# GAT8_PCB.net
KiCad netlist of a schematic drawn in EAGLE
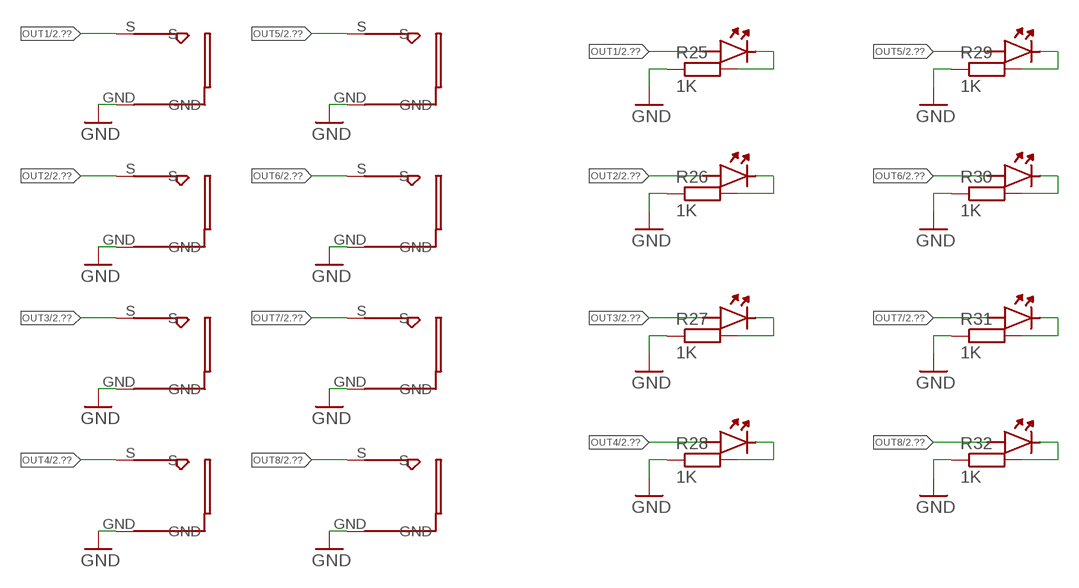
[diagram p0: schematic, sheet 1]
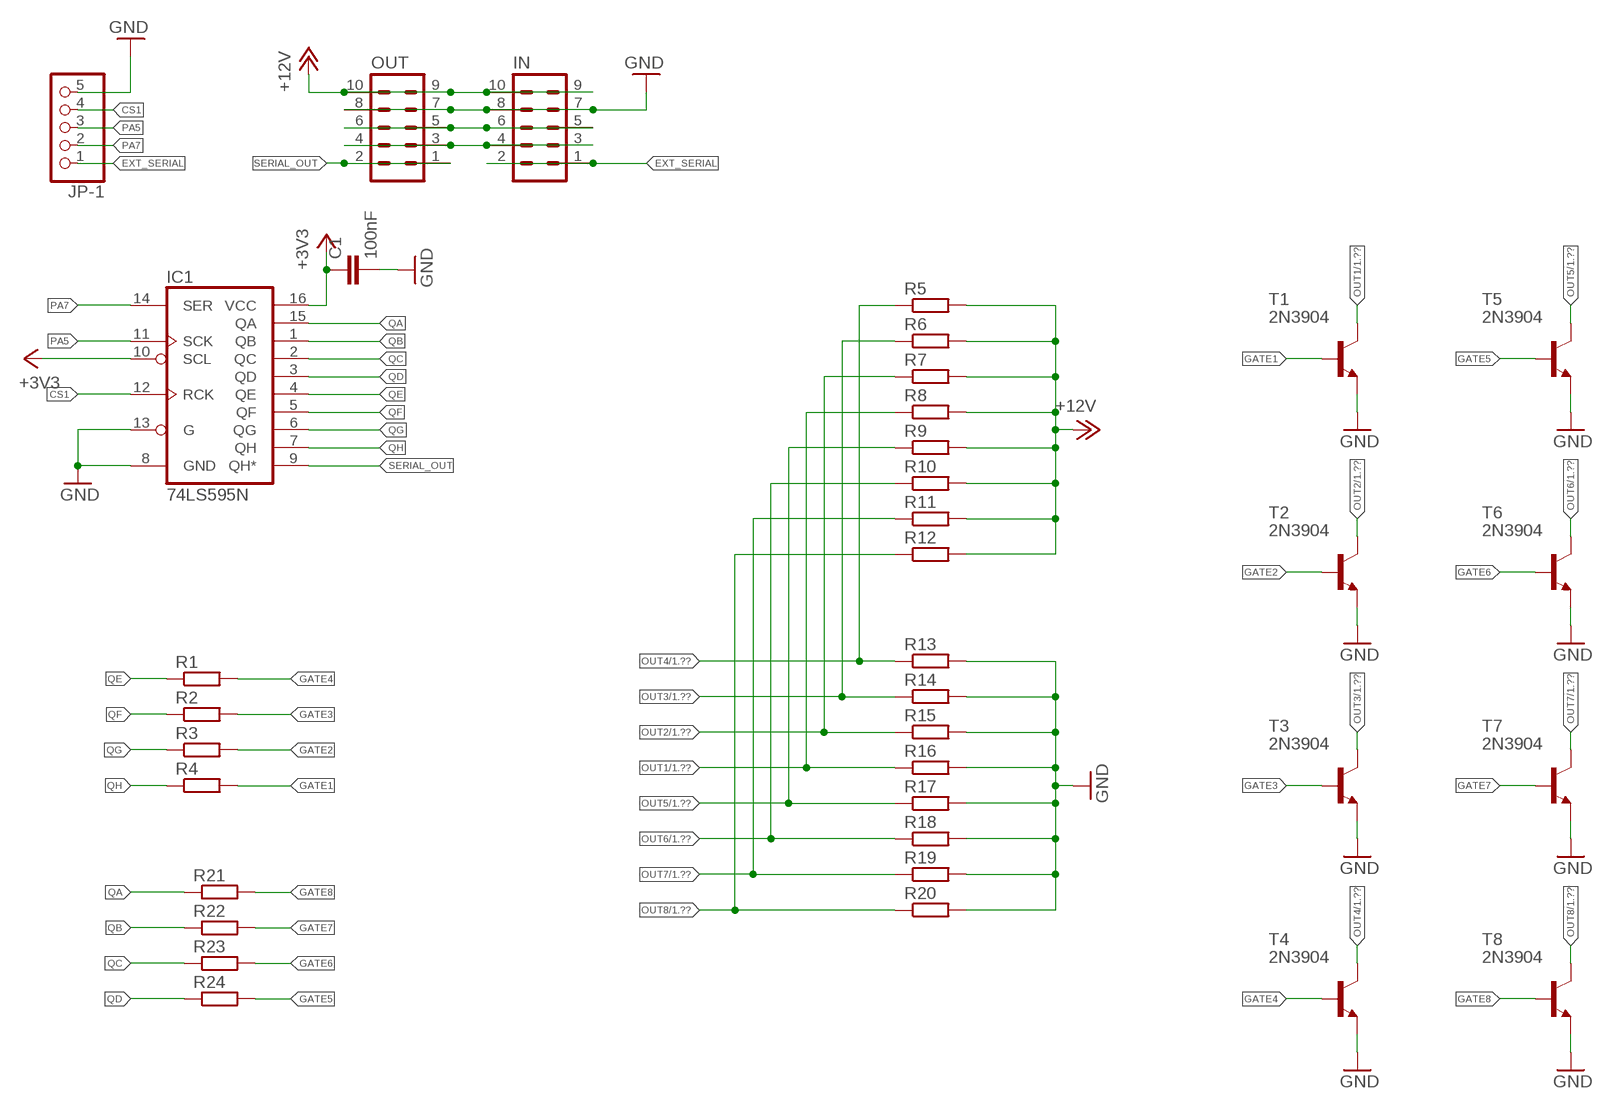
[diagram p1: schematic, sheet 2]
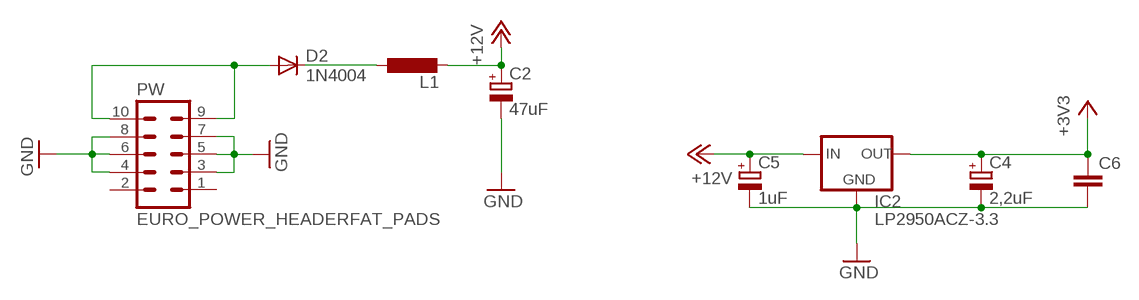
[diagram p2: schematic, sheet 3]

(export (version "E")
  (design (tool "Eeschema 10.0.6"))
  (components
    (comp (ref "C1")
      (value "100nF")
      (footprint "eagle-import:C1206K")
      (libsource (lib "eagle-import") (part "C-EUC1206K"))
    )
    (comp (ref "IC1")
      (value "74LS595N")
      (footprint "eagle-import:DIL16")
      (libsource (lib "eagle-import") (part "74595NLS"))
    )
    (comp (ref "IN")
      (value "ML10")
      (footprint "eagle-import:ML10")
      (fields (field (name "OC_FARNELL") "unknown") (field (name "OC_NEWARK") "unknown"))
      (libsource (lib "eagle-import") (part "ML10"))
    )
    (comp (ref "JP-1")
      (value "PINHD-1X5_2.54")
      (footprint "eagle-import:1X05")
      (libsource (lib "eagle-import") (part "PINHD-1X5_2.54"))
    )
    (comp (ref "OUT")
      (value "ML10")
      (footprint "eagle-import:ML10")
      (libsource (lib "eagle-import") (part "ML10"))
    )
    (comp (ref "R1")
      (value "R-EU_R1206")
      (footprint "eagle-import:R1206")
      (libsource (lib "eagle-import") (part "R-EU_R1206"))
    )
    (comp (ref "R2")
      (value "R-EU_R1206")
      (footprint "eagle-import:R1206")
      (libsource (lib "eagle-import") (part "R-EU_R1206"))
    )
    (comp (ref "R3")
      (value "R-EU_R1206")
      (footprint "eagle-import:R1206")
      (libsource (lib "eagle-import") (part "R-EU_R1206"))
    )
    (comp (ref "R4")
      (value "R-EU_R1206")
      (footprint "eagle-import:R1206")
      (libsource (lib "eagle-import") (part "R-EU_R1206"))
    )
    (comp (ref "R5")
      (value "R-EU_R1206")
      (footprint "eagle-import:R1206")
      (libsource (lib "eagle-import") (part "R-EU_R1206"))
    )
    (comp (ref "R6")
      (value "R-EU_R1206")
      (footprint "eagle-import:R1206")
      (libsource (lib "eagle-import") (part "R-EU_R1206"))
    )
    (comp (ref "R7")
      (value "R-EU_R1206")
      (footprint "eagle-import:R1206")
      (libsource (lib "eagle-import") (part "R-EU_R1206"))
    )
    (comp (ref "R8")
      (value "R-EU_R1206")
      (footprint "eagle-import:R1206")
      (libsource (lib "eagle-import") (part "R-EU_R1206"))
    )
    (comp (ref "R9")
      (value "R-EU_R1206")
      (footprint "eagle-import:R1206")
      (libsource (lib "eagle-import") (part "R-EU_R1206"))
    )
    (comp (ref "R10")
      (value "R-EU_R1206")
      (footprint "eagle-import:R1206")
      (libsource (lib "eagle-import") (part "R-EU_R1206"))
    )
    (comp (ref "R11")
      (value "R-EU_R1206")
      (footprint "eagle-import:R1206")
      (libsource (lib "eagle-import") (part "R-EU_R1206"))
    )
    (comp (ref "R12")
      (value "R-EU_R1206")
      (footprint "eagle-import:R1206")
      (libsource (lib "eagle-import") (part "R-EU_R1206"))
    )
    (comp (ref "R13")
      (value "R-EU_R1206")
      (footprint "eagle-import:R1206")
      (libsource (lib "eagle-import") (part "R-EU_R1206"))
    )
    (comp (ref "R14")
      (value "R-EU_R1206")
      (footprint "eagle-import:R1206")
      (libsource (lib "eagle-import") (part "R-EU_R1206"))
    )
    (comp (ref "R15")
      (value "R-EU_R1206")
      (footprint "eagle-import:R1206")
      (libsource (lib "eagle-import") (part "R-EU_R1206"))
    )
    (comp (ref "R16")
      (value "R-EU_R1206")
      (footprint "eagle-import:R1206")
      (libsource (lib "eagle-import") (part "R-EU_R1206"))
    )
    (comp (ref "R17")
      (value "R-EU_R1206")
      (footprint "eagle-import:R1206")
      (libsource (lib "eagle-import") (part "R-EU_R1206"))
    )
    (comp (ref "R18")
      (value "R-EU_R1206")
      (footprint "eagle-import:R1206")
      (libsource (lib "eagle-import") (part "R-EU_R1206"))
    )
    (comp (ref "R19")
      (value "R-EU_R1206")
      (footprint "eagle-import:R1206")
      (libsource (lib "eagle-import") (part "R-EU_R1206"))
    )
    (comp (ref "R20")
      (value "R-EU_R1206")
      (footprint "eagle-import:R1206")
      (libsource (lib "eagle-import") (part "R-EU_R1206"))
    )
    (comp (ref "R21")
      (value "R-EU_R1206")
      (footprint "eagle-import:R1206")
      (libsource (lib "eagle-import") (part "R-EU_R1206"))
    )
    (comp (ref "R22")
      (value "R-EU_R1206")
      (footprint "eagle-import:R1206")
      (libsource (lib "eagle-import") (part "R-EU_R1206"))
    )
    (comp (ref "R23")
      (value "R-EU_R1206")
      (footprint "eagle-import:R1206")
      (libsource (lib "eagle-import") (part "R-EU_R1206"))
    )
    (comp (ref "R24")
      (value "R-EU_R1206")
      (footprint "eagle-import:R1206")
      (libsource (lib "eagle-import") (part "R-EU_R1206"))
    )
    (comp (ref "T1")
      (value "2N3904")
      (footprint "eagle-import:TO92")
      (libsource (lib "eagle-import") (part "2N3904"))
    )
    (comp (ref "T2")
      (value "2N3904")
      (footprint "eagle-import:TO92")
      (libsource (lib "eagle-import") (part "2N3904"))
    )
    (comp (ref "T3")
      (value "2N3904")
      (footprint "eagle-import:TO92")
      (libsource (lib "eagle-import") (part "2N3904"))
    )
    (comp (ref "T4")
      (value "2N3904")
      (footprint "eagle-import:TO92")
      (libsource (lib "eagle-import") (part "2N3904"))
    )
    (comp (ref "T5")
      (value "2N3904")
      (footprint "eagle-import:TO92")
      (libsource (lib "eagle-import") (part "2N3904"))
    )
    (comp (ref "T6")
      (value "2N3904")
      (footprint "eagle-import:TO92")
      (libsource (lib "eagle-import") (part "2N3904"))
    )
    (comp (ref "T7")
      (value "2N3904")
      (footprint "eagle-import:TO92")
      (libsource (lib "eagle-import") (part "2N3904"))
    )
    (comp (ref "T8")
      (value "2N3904")
      (footprint "eagle-import:TO92")
      (libsource (lib "eagle-import") (part "2N3904"))
    )
    (comp (ref "LED8")
      (value "LED")
      (footprint "eagle-import:LED")
      (libsource (lib "eagle-import") (part "LED"))
    )
    (comp (ref "OUT1")
      (value "PJ302M")
      (footprint "eagle-import:PJ302M")
      (libsource (lib "eagle-import") (part "PJ302M"))
    )
    (comp (ref "OUT2")
      (value "PJ302M")
      (footprint "eagle-import:PJ302M")
      (libsource (lib "eagle-import") (part "PJ302M"))
    )
    (comp (ref "OUT3")
      (value "PJ302M")
      (footprint "eagle-import:PJ302M")
      (libsource (lib "eagle-import") (part "PJ302M"))
    )
    (comp (ref "OUT4")
      (value "PJ302M")
      (footprint "eagle-import:PJ302M")
      (libsource (lib "eagle-import") (part "PJ302M"))
    )
    (comp (ref "OUT5")
      (value "PJ302M")
      (footprint "eagle-import:PJ302M")
      (libsource (lib "eagle-import") (part "PJ302M"))
    )
    (comp (ref "OUT6")
      (value "PJ302M")
      (footprint "eagle-import:PJ302M")
      (libsource (lib "eagle-import") (part "PJ302M"))
    )
    (comp (ref "OUT7")
      (value "PJ302M")
      (footprint "eagle-import:PJ302M")
      (libsource (lib "eagle-import") (part "PJ302M"))
    )
    (comp (ref "OUT8")
      (value "PJ302M")
      (footprint "eagle-import:PJ302M")
      (libsource (lib "eagle-import") (part "PJ302M"))
    )
    (comp (ref "R25")
      (value "1K")
      (footprint "eagle-import:R1206")
      (libsource (lib "eagle-import") (part "R-EU_R1206"))
    )
    (comp (ref "R26")
      (value "1K")
      (footprint "eagle-import:R1206")
      (libsource (lib "eagle-import") (part "R-EU_R1206"))
    )
    (comp (ref "R27")
      (value "1K")
      (footprint "eagle-import:R1206")
      (libsource (lib "eagle-import") (part "R-EU_R1206"))
    )
    (comp (ref "R28")
      (value "1K")
      (footprint "eagle-import:R1206")
      (libsource (lib "eagle-import") (part "R-EU_R1206"))
    )
    (comp (ref "R29")
      (value "1K")
      (footprint "eagle-import:R1206")
      (libsource (lib "eagle-import") (part "R-EU_R1206"))
    )
    (comp (ref "R30")
      (value "1K")
      (footprint "eagle-import:R1206")
      (libsource (lib "eagle-import") (part "R-EU_R1206"))
    )
    (comp (ref "R31")
      (value "1K")
      (footprint "eagle-import:R1206")
      (libsource (lib "eagle-import") (part "R-EU_R1206"))
    )
    (comp (ref "R32")
      (value "1K")
      (footprint "eagle-import:R1206")
      (libsource (lib "eagle-import") (part "R-EU_R1206"))
    )
    (comp (ref "U$1")
      (value "LED")
      (footprint "eagle-import:LED")
      (libsource (lib "eagle-import") (part "LED"))
    )
    (comp (ref "U$2")
      (value "LED")
      (footprint "eagle-import:LED")
      (libsource (lib "eagle-import") (part "LED"))
    )
    (comp (ref "U$3")
      (value "LED")
      (footprint "eagle-import:LED")
      (libsource (lib "eagle-import") (part "LED"))
    )
    (comp (ref "U$4")
      (value "LED")
      (footprint "eagle-import:LED")
      (libsource (lib "eagle-import") (part "LED"))
    )
    (comp (ref "U$5")
      (value "LED")
      (footprint "eagle-import:LED")
      (libsource (lib "eagle-import") (part "LED"))
    )
    (comp (ref "U$6")
      (value "LED")
      (footprint "eagle-import:LED")
      (libsource (lib "eagle-import") (part "LED"))
    )
    (comp (ref "U$7")
      (value "LED")
      (footprint "eagle-import:LED")
      (libsource (lib "eagle-import") (part "LED"))
    )
    (comp (ref "C2")
      (value "47uF")
      (footprint "eagle-import:E2-5")
      (libsource (lib "eagle-import") (part "CPOL-EUE2-5"))
    )
    (comp (ref "C4")
      (value "2,2uF")
      (footprint "eagle-import:E2-5")
      (libsource (lib "eagle-import") (part "CPOL-EUE2-5"))
    )
    (comp (ref "C5")
      (value "1uF")
      (footprint "eagle-import:E2-5")
      (libsource (lib "eagle-import") (part "CPOL-EUE2-5"))
    )
    (comp (ref "C6")
      (value "C-EUC1206K")
      (footprint "eagle-import:C1206K")
      (libsource (lib "eagle-import") (part "C-EUC1206K"))
    )
    (comp (ref "D2")
      (value "1N4004")
      (footprint "eagle-import:DO41-10")
      (libsource (lib "eagle-import") (part "1N4004"))
    )
    (comp (ref "IC2")
      (value "LP2950ACZ-3.3")
      (footprint "eagle-import:TO92")
      (libsource (lib "eagle-import") (part "LP2950?ACZ-3.3"))
    )
    (comp (ref "L1")
      (value "L-EU0207/10")
      (footprint "eagle-import:0207_10")
      (libsource (lib "eagle-import") (part "L-EU0207/10"))
    )
    (comp (ref "PW")
      (value "EURO_POWER_HEADERFAT_PADS")
      (footprint "eagle-import:EURO_PWR_HEADER_FAT")
      (libsource (lib "eagle-import") (part "EURO_POWER_HEADERFAT_PADS"))
    )
  )
  (nets
    (net (code "1") (name "+3V3") (class "Default")
      (node (ref "C1") (pin "1") (pinfunction "1_1") (pintype "passive"))
      (node (ref "C4") (pin "+") (pinfunction "+_+") (pintype "passive"))
      (node (ref "C6") (pin "1") (pinfunction "1_1") (pintype "passive"))
      (node (ref "IC1") (pin "10") (pinfunction "SCL_10") (pintype "input"))
      (node (ref "IC1") (pin "16") (pinfunction "VCC_16") (pintype "power_in"))
      (node (ref "IC2") (pin "1") (pinfunction "OUT_1") (pintype "passive"))
    )
    (net (code "2") (name "+12V") (class "Default")
      (node (ref "C2") (pin "+") (pinfunction "+_+") (pintype "passive"))
      (node (ref "C5") (pin "+") (pinfunction "+_+") (pintype "passive"))
      (node (ref "IC2") (pin "3") (pinfunction "IN_3") (pintype "input"))
      (node (ref "IN") (pin "10") (pinfunction "10_10") (pintype "passive"))
      (node (ref "IN") (pin "9") (pinfunction "9_9") (pintype "passive"))
      (node (ref "L1") (pin "2") (pinfunction "2_2") (pintype "passive"))
      (node (ref "OUT") (pin "10") (pinfunction "10_10") (pintype "passive"))
      (node (ref "OUT") (pin "9") (pinfunction "9_9") (pintype "passive"))
      (node (ref "R10") (pin "2") (pinfunction "2_2") (pintype "passive"))
      (node (ref "R11") (pin "2") (pinfunction "2_2") (pintype "passive"))
      (node (ref "R12") (pin "2") (pinfunction "2_2") (pintype "passive"))
      (node (ref "R5") (pin "2") (pinfunction "2_2") (pintype "passive"))
      (node (ref "R6") (pin "2") (pinfunction "2_2") (pintype "passive"))
      (node (ref "R7") (pin "2") (pinfunction "2_2") (pintype "passive"))
      (node (ref "R8") (pin "2") (pinfunction "2_2") (pintype "passive"))
      (node (ref "R9") (pin "2") (pinfunction "2_2") (pintype "passive"))
    )
    (net (code "3") (name "CS1") (class "Default")
      (node (ref "IC1") (pin "12") (pinfunction "RCK_12") (pintype "input"))
      (node (ref "JP-1") (pin "4") (pinfunction "4_4") (pintype "passive"))
    )
    (net (code "4") (name "EXT_SERIAL") (class "Default")
      (node (ref "IN") (pin "1") (pinfunction "1_1") (pintype "passive"))
      (node (ref "IN") (pin "2") (pinfunction "2_2") (pintype "passive"))
      (node (ref "JP-1") (pin "1") (pinfunction "1_1") (pintype "passive"))
    )
    (net (code "5") (name "GATE1") (class "Default")
      (node (ref "R4") (pin "2") (pinfunction "2_2") (pintype "passive"))
      (node (ref "T1") (pin "2") (pinfunction "B_2") (pintype "passive"))
    )
    (net (code "6") (name "GATE2") (class "Default")
      (node (ref "R3") (pin "2") (pinfunction "2_2") (pintype "passive"))
      (node (ref "T2") (pin "2") (pinfunction "B_2") (pintype "passive"))
    )
    (net (code "7") (name "GATE3") (class "Default")
      (node (ref "R2") (pin "2") (pinfunction "2_2") (pintype "passive"))
      (node (ref "T3") (pin "2") (pinfunction "B_2") (pintype "passive"))
    )
    (net (code "8") (name "GATE4") (class "Default")
      (node (ref "R1") (pin "2") (pinfunction "2_2") (pintype "passive"))
      (node (ref "T4") (pin "2") (pinfunction "B_2") (pintype "passive"))
    )
    (net (code "9") (name "GATE5") (class "Default")
      (node (ref "R24") (pin "2") (pinfunction "2_2") (pintype "passive"))
      (node (ref "T5") (pin "2") (pinfunction "B_2") (pintype "passive"))
    )
    (net (code "10") (name "GATE6") (class "Default")
      (node (ref "R23") (pin "2") (pinfunction "2_2") (pintype "passive"))
      (node (ref "T6") (pin "2") (pinfunction "B_2") (pintype "passive"))
    )
    (net (code "11") (name "GATE7") (class "Default")
      (node (ref "R22") (pin "2") (pinfunction "2_2") (pintype "passive"))
      (node (ref "T7") (pin "2") (pinfunction "B_2") (pintype "passive"))
    )
    (net (code "12") (name "GATE8") (class "Default")
      (node (ref "R21") (pin "2") (pinfunction "2_2") (pintype "passive"))
      (node (ref "T8") (pin "2") (pinfunction "B_2") (pintype "passive"))
    )
    (net (code "13") (name "GND") (class "Default")
      (node (ref "C1") (pin "2") (pinfunction "2_2") (pintype "passive"))
      (node (ref "C2") (pin "-") (pinfunction "-_-") (pintype "passive"))
      (node (ref "C4") (pin "-") (pinfunction "-_-") (pintype "passive"))
      (node (ref "C5") (pin "-") (pinfunction "-_-") (pintype "passive"))
      (node (ref "C6") (pin "2") (pinfunction "2_2") (pintype "passive"))
      (node (ref "IC1") (pin "13") (pinfunction "G_13") (pintype "input"))
      (node (ref "IC1") (pin "8") (pinfunction "GND_8") (pintype "power_in"))
      (node (ref "IC2") (pin "2") (pinfunction "GND_2") (pintype "input"))
      (node (ref "IN") (pin "7") (pinfunction "7_7") (pintype "passive"))
      (node (ref "IN") (pin "8") (pinfunction "8_8") (pintype "passive"))
      (node (ref "JP-1") (pin "5") (pinfunction "5_5") (pintype "passive"))
      (node (ref "OUT") (pin "7") (pinfunction "7_7") (pintype "passive"))
      (node (ref "OUT") (pin "8") (pinfunction "8_8") (pintype "passive"))
      (node (ref "OUT1") (pin "GND") (pinfunction "GND_GND") (pintype "bidirectional"))
      (node (ref "OUT2") (pin "GND") (pinfunction "GND_GND") (pintype "bidirectional"))
      (node (ref "OUT3") (pin "GND") (pinfunction "GND_GND") (pintype "bidirectional"))
      (node (ref "OUT4") (pin "GND") (pinfunction "GND_GND") (pintype "bidirectional"))
      (node (ref "OUT5") (pin "GND") (pinfunction "GND_GND") (pintype "bidirectional"))
      (node (ref "OUT6") (pin "GND") (pinfunction "GND_GND") (pintype "bidirectional"))
      (node (ref "OUT7") (pin "GND") (pinfunction "GND_GND") (pintype "bidirectional"))
      (node (ref "OUT8") (pin "GND") (pinfunction "GND_GND") (pintype "bidirectional"))
      (node (ref "PW") (pin "3") (pinfunction "3_3") (pintype "passive"))
      (node (ref "PW") (pin "4") (pinfunction "4_4") (pintype "passive"))
      (node (ref "PW") (pin "5") (pinfunction "5_5") (pintype "passive"))
      (node (ref "PW") (pin "6") (pinfunction "6_6") (pintype "passive"))
      (node (ref "PW") (pin "7") (pinfunction "7_7") (pintype "passive"))
      (node (ref "PW") (pin "8") (pinfunction "8_8") (pintype "passive"))
      (node (ref "R13") (pin "2") (pinfunction "2_2") (pintype "passive"))
      (node (ref "R14") (pin "2") (pinfunction "2_2") (pintype "passive"))
      (node (ref "R15") (pin "2") (pinfunction "2_2") (pintype "passive"))
      (node (ref "R16") (pin "2") (pinfunction "2_2") (pintype "passive"))
      (node (ref "R17") (pin "2") (pinfunction "2_2") (pintype "passive"))
      (node (ref "R18") (pin "2") (pinfunction "2_2") (pintype "passive"))
      (node (ref "R19") (pin "2") (pinfunction "2_2") (pintype "passive"))
      (node (ref "R20") (pin "2") (pinfunction "2_2") (pintype "passive"))
      (node (ref "R25") (pin "1") (pinfunction "1_1") (pintype "passive"))
      (node (ref "R26") (pin "1") (pinfunction "1_1") (pintype "passive"))
      (node (ref "R27") (pin "1") (pinfunction "1_1") (pintype "passive"))
      (node (ref "R28") (pin "1") (pinfunction "1_1") (pintype "passive"))
      (node (ref "R29") (pin "1") (pinfunction "1_1") (pintype "passive"))
      (node (ref "R30") (pin "1") (pinfunction "1_1") (pintype "passive"))
      (node (ref "R31") (pin "1") (pinfunction "1_1") (pintype "passive"))
      (node (ref "R32") (pin "1") (pinfunction "1_1") (pintype "passive"))
      (node (ref "T1") (pin "3") (pinfunction "E_3") (pintype "passive"))
      (node (ref "T2") (pin "3") (pinfunction "E_3") (pintype "passive"))
      (node (ref "T3") (pin "3") (pinfunction "E_3") (pintype "passive"))
      (node (ref "T4") (pin "3") (pinfunction "E_3") (pintype "passive"))
      (node (ref "T5") (pin "3") (pinfunction "E_3") (pintype "passive"))
      (node (ref "T6") (pin "3") (pinfunction "E_3") (pintype "passive"))
      (node (ref "T7") (pin "3") (pinfunction "E_3") (pintype "passive"))
      (node (ref "T8") (pin "3") (pinfunction "E_3") (pintype "passive"))
    )
    (net (code "14") (name "Net-(D2-PadA)") (class "Default")
      (node (ref "D2") (pin "A") (pinfunction "A_A") (pintype "passive"))
      (node (ref "PW") (pin "10") (pinfunction "10_10") (pintype "passive"))
      (node (ref "PW") (pin "9") (pinfunction "9_9") (pintype "passive"))
    )
    (net (code "15") (name "Net-(D2-PadC)") (class "Default")
      (node (ref "D2") (pin "C") (pinfunction "C_C") (pintype "passive"))
      (node (ref "L1") (pin "1") (pinfunction "1_1") (pintype "passive"))
    )
    (net (code "16") (name "Net-(IN-Pad3)") (class "Default")
      (node (ref "IN") (pin "3") (pinfunction "3_3") (pintype "passive"))
      (node (ref "IN") (pin "4") (pinfunction "4_4") (pintype "passive"))
      (node (ref "OUT") (pin "3") (pinfunction "3_3") (pintype "passive"))
      (node (ref "OUT") (pin "4") (pinfunction "4_4") (pintype "passive"))
    )
    (net (code "17") (name "Net-(IN-Pad5)") (class "Default")
      (node (ref "IN") (pin "5") (pinfunction "5_5") (pintype "passive"))
      (node (ref "IN") (pin "6") (pinfunction "6_6") (pintype "passive"))
      (node (ref "OUT") (pin "5") (pinfunction "5_5") (pintype "passive"))
      (node (ref "OUT") (pin "6") (pinfunction "6_6") (pintype "passive"))
    )
    (net (code "18") (name "Net-(LED8-PadGND)") (class "Default")
      (node (ref "LED8") (pin "GND") (pinfunction "GND_GND") (pintype "output"))
      (node (ref "R32") (pin "2") (pinfunction "2_2") (pintype "passive"))
    )
    (net (code "19") (name "Net-(R25-Pad2)") (class "Default")
      (node (ref "R25") (pin "2") (pinfunction "2_2") (pintype "passive"))
      (node (ref "U$1") (pin "GND") (pinfunction "GND_GND") (pintype "output"))
    )
    (net (code "20") (name "Net-(R26-Pad2)") (class "Default")
      (node (ref "R26") (pin "2") (pinfunction "2_2") (pintype "passive"))
      (node (ref "U$2") (pin "GND") (pinfunction "GND_GND") (pintype "output"))
    )
    (net (code "21") (name "Net-(R27-Pad2)") (class "Default")
      (node (ref "R27") (pin "2") (pinfunction "2_2") (pintype "passive"))
      (node (ref "U$3") (pin "GND") (pinfunction "GND_GND") (pintype "output"))
    )
    (net (code "22") (name "Net-(R28-Pad2)") (class "Default")
      (node (ref "R28") (pin "2") (pinfunction "2_2") (pintype "passive"))
      (node (ref "U$4") (pin "GND") (pinfunction "GND_GND") (pintype "output"))
    )
    (net (code "23") (name "Net-(R29-Pad2)") (class "Default")
      (node (ref "R29") (pin "2") (pinfunction "2_2") (pintype "passive"))
      (node (ref "U$5") (pin "GND") (pinfunction "GND_GND") (pintype "output"))
    )
    (net (code "24") (name "Net-(R30-Pad2)") (class "Default")
      (node (ref "R30") (pin "2") (pinfunction "2_2") (pintype "passive"))
      (node (ref "U$6") (pin "GND") (pinfunction "GND_GND") (pintype "output"))
    )
    (net (code "25") (name "Net-(R31-Pad2)") (class "Default")
      (node (ref "R31") (pin "2") (pinfunction "2_2") (pintype "passive"))
      (node (ref "U$7") (pin "GND") (pinfunction "GND_GND") (pintype "output"))
    )
    (net (code "26") (name "OUT1") (class "Default")
      (node (ref "OUT1") (pin "S") (pinfunction "S_S") (pintype "bidirectional"))
      (node (ref "R16") (pin "1") (pinfunction "1_1") (pintype "passive"))
      (node (ref "R8") (pin "1") (pinfunction "1_1") (pintype "passive"))
      (node (ref "T1") (pin "1") (pinfunction "C_1") (pintype "passive"))
      (node (ref "U$1") (pin "S") (pinfunction "S_S") (pintype "input"))
    )
    (net (code "27") (name "OUT2") (class "Default")
      (node (ref "OUT2") (pin "S") (pinfunction "S_S") (pintype "bidirectional"))
      (node (ref "R15") (pin "1") (pinfunction "1_1") (pintype "passive"))
      (node (ref "R7") (pin "1") (pinfunction "1_1") (pintype "passive"))
      (node (ref "T2") (pin "1") (pinfunction "C_1") (pintype "passive"))
      (node (ref "U$2") (pin "S") (pinfunction "S_S") (pintype "input"))
    )
    (net (code "28") (name "OUT3") (class "Default")
      (node (ref "OUT3") (pin "S") (pinfunction "S_S") (pintype "bidirectional"))
      (node (ref "R14") (pin "1") (pinfunction "1_1") (pintype "passive"))
      (node (ref "R6") (pin "1") (pinfunction "1_1") (pintype "passive"))
      (node (ref "T3") (pin "1") (pinfunction "C_1") (pintype "passive"))
      (node (ref "U$3") (pin "S") (pinfunction "S_S") (pintype "input"))
    )
    (net (code "29") (name "OUT4") (class "Default")
      (node (ref "OUT4") (pin "S") (pinfunction "S_S") (pintype "bidirectional"))
      (node (ref "R13") (pin "1") (pinfunction "1_1") (pintype "passive"))
      (node (ref "R5") (pin "1") (pinfunction "1_1") (pintype "passive"))
      (node (ref "T4") (pin "1") (pinfunction "C_1") (pintype "passive"))
      (node (ref "U$4") (pin "S") (pinfunction "S_S") (pintype "input"))
    )
    (net (code "30") (name "OUT5") (class "Default")
      (node (ref "OUT5") (pin "S") (pinfunction "S_S") (pintype "bidirectional"))
      (node (ref "R17") (pin "1") (pinfunction "1_1") (pintype "passive"))
      (node (ref "R9") (pin "1") (pinfunction "1_1") (pintype "passive"))
      (node (ref "T5") (pin "1") (pinfunction "C_1") (pintype "passive"))
      (node (ref "U$5") (pin "S") (pinfunction "S_S") (pintype "input"))
    )
    (net (code "31") (name "OUT6") (class "Default")
      (node (ref "OUT6") (pin "S") (pinfunction "S_S") (pintype "bidirectional"))
      (node (ref "R10") (pin "1") (pinfunction "1_1") (pintype "passive"))
      (node (ref "R18") (pin "1") (pinfunction "1_1") (pintype "passive"))
      (node (ref "T6") (pin "1") (pinfunction "C_1") (pintype "passive"))
      (node (ref "U$6") (pin "S") (pinfunction "S_S") (pintype "input"))
    )
    (net (code "32") (name "OUT7") (class "Default")
      (node (ref "OUT7") (pin "S") (pinfunction "S_S") (pintype "bidirectional"))
      (node (ref "R11") (pin "1") (pinfunction "1_1") (pintype "passive"))
      (node (ref "R19") (pin "1") (pinfunction "1_1") (pintype "passive"))
      (node (ref "T7") (pin "1") (pinfunction "C_1") (pintype "passive"))
      (node (ref "U$7") (pin "S") (pinfunction "S_S") (pintype "input"))
    )
    (net (code "33") (name "OUT8") (class "Default")
      (node (ref "LED8") (pin "S") (pinfunction "S_S") (pintype "input"))
      (node (ref "OUT8") (pin "S") (pinfunction "S_S") (pintype "bidirectional"))
      (node (ref "R12") (pin "1") (pinfunction "1_1") (pintype "passive"))
      (node (ref "R20") (pin "1") (pinfunction "1_1") (pintype "passive"))
      (node (ref "T8") (pin "1") (pinfunction "C_1") (pintype "passive"))
    )
    (net (code "34") (name "PA5") (class "Default")
      (node (ref "IC1") (pin "11") (pinfunction "SCK_11") (pintype "input"))
      (node (ref "JP-1") (pin "3") (pinfunction "3_3") (pintype "passive"))
    )
    (net (code "35") (name "PA7") (class "Default")
      (node (ref "IC1") (pin "14") (pinfunction "SER_14") (pintype "input"))
      (node (ref "JP-1") (pin "2") (pinfunction "2_2") (pintype "passive"))
    )
    (net (code "36") (name "QA") (class "Default")
      (node (ref "IC1") (pin "15") (pinfunction "QA_15") (pintype "tri_state"))
      (node (ref "R21") (pin "1") (pinfunction "1_1") (pintype "passive"))
    )
    (net (code "37") (name "QB") (class "Default")
      (node (ref "IC1") (pin "1") (pinfunction "QB_1") (pintype "tri_state"))
      (node (ref "R22") (pin "1") (pinfunction "1_1") (pintype "passive"))
    )
    (net (code "38") (name "QC") (class "Default")
      (node (ref "IC1") (pin "2") (pinfunction "QC_2") (pintype "tri_state"))
      (node (ref "R23") (pin "1") (pinfunction "1_1") (pintype "passive"))
    )
    (net (code "39") (name "QD") (class "Default")
      (node (ref "IC1") (pin "3") (pinfunction "QD_3") (pintype "tri_state"))
      (node (ref "R24") (pin "1") (pinfunction "1_1") (pintype "passive"))
    )
    (net (code "40") (name "QE") (class "Default")
      (node (ref "IC1") (pin "4") (pinfunction "QE_4") (pintype "tri_state"))
      (node (ref "R1") (pin "1") (pinfunction "1_1") (pintype "passive"))
    )
    (net (code "41") (name "QF") (class "Default")
      (node (ref "IC1") (pin "5") (pinfunction "QF_5") (pintype "tri_state"))
      (node (ref "R2") (pin "1") (pinfunction "1_1") (pintype "passive"))
    )
    (net (code "42") (name "QG") (class "Default")
      (node (ref "IC1") (pin "6") (pinfunction "QG_6") (pintype "tri_state"))
      (node (ref "R3") (pin "1") (pinfunction "1_1") (pintype "passive"))
    )
    (net (code "43") (name "QH") (class "Default")
      (node (ref "IC1") (pin "7") (pinfunction "QH_7") (pintype "tri_state"))
      (node (ref "R4") (pin "1") (pinfunction "1_1") (pintype "passive"))
    )
    (net (code "44") (name "SERIAL_OUT") (class "Default")
      (node (ref "IC1") (pin "9") (pinfunction "QH*_9") (pintype "tri_state"))
      (node (ref "OUT") (pin "1") (pinfunction "1_1") (pintype "passive"))
      (node (ref "OUT") (pin "2") (pinfunction "2_2") (pintype "passive"))
    )
    (net (code "45") (name "unconnected-(PW-Pad1)") (class "Default")
      (node (ref "PW") (pin "1") (pinfunction "1_1") (pintype "passive"))
    )
    (net (code "46") (name "unconnected-(PW-Pad2)") (class "Default")
      (node (ref "PW") (pin "2") (pinfunction "2_2") (pintype "passive"))
    )
  )
)
